# v_0_2.net
KiCad netlist of a schematic drawn in EAGLE
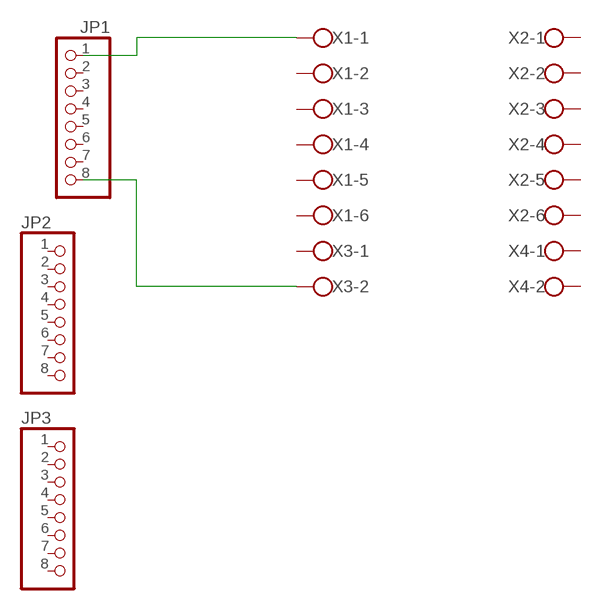
[diagram p0: schematic, sheet 1]

(export (version "E")
  (design (tool "Eeschema 10.0.6"))
  (components
    (comp (ref "JP1")
      (value "PINHD-1X8")
      (footprint "eagle-import:1X08")
      (libsource (lib "eagle-import") (part "PINHD-1X8"))
    )
    (comp (ref "JP2")
      (value "PINHD-1X8")
      (footprint "eagle-import:1X08")
      (libsource (lib "eagle-import") (part "PINHD-1X8"))
    )
    (comp (ref "JP3")
      (value "PINHD-1X8")
      (footprint "eagle-import:1X08")
      (libsource (lib "eagle-import") (part "PINHD-1X8"))
    )
    (comp (ref "X1")
      (value "W237-136")
      (footprint "eagle-import:W237-136")
      (fields (field (name "MPN") "237-136"))
      (libsource (lib "eagle-import") (part "W237-136"))
    )
    (comp (ref "X2")
      (value "W237-136")
      (footprint "eagle-import:W237-136")
      (fields (field (name "MPN") "237-136"))
      (libsource (lib "eagle-import") (part "W237-136"))
    )
    (comp (ref "X3")
      (value "W237-136")
      (footprint "eagle-import:W237-136")
      (fields (field (name "MPN") "237-136"))
      (libsource (lib "eagle-import") (part "W237-136"))
    )
    (comp (ref "X4")
      (value "W237-136")
      (footprint "eagle-import:W237-136")
      (fields (field (name "MPN") "237-136"))
      (libsource (lib "eagle-import") (part "W237-136"))
    )
  )
  (nets
    (net (code "1") (name "Net-(X1A-KL)") (class "Default")
      (node (ref "JP1") (pin "1") (pinfunction "1_1") (pintype "passive"))
      (node (ref "X1") (pin "1") (pinfunction "KL_1") (pintype "passive"))
    )
    (net (code "2") (name "Net-(X3B-KL)") (class "Default")
      (node (ref "JP1") (pin "8") (pinfunction "8_8") (pintype "passive"))
      (node (ref "X3") (pin "2") (pinfunction "KL_2") (pintype "passive"))
    )
    (net (code "3") (name "unconnected-(JP1-Pad2)") (class "Default")
      (node (ref "JP1") (pin "2") (pinfunction "2_2") (pintype "passive"))
    )
    (net (code "4") (name "unconnected-(JP1-Pad3)") (class "Default")
      (node (ref "JP1") (pin "3") (pinfunction "3_3") (pintype "passive"))
    )
    (net (code "5") (name "unconnected-(JP1-Pad4)") (class "Default")
      (node (ref "JP1") (pin "4") (pinfunction "4_4") (pintype "passive"))
    )
    (net (code "6") (name "unconnected-(JP1-Pad5)") (class "Default")
      (node (ref "JP1") (pin "5") (pinfunction "5_5") (pintype "passive"))
    )
    (net (code "7") (name "unconnected-(JP1-Pad6)") (class "Default")
      (node (ref "JP1") (pin "6") (pinfunction "6_6") (pintype "passive"))
    )
    (net (code "8") (name "unconnected-(JP1-Pad7)") (class "Default")
      (node (ref "JP1") (pin "7") (pinfunction "7_7") (pintype "passive"))
    )
    (net (code "9") (name "unconnected-(JP2-Pad1)") (class "Default")
      (node (ref "JP2") (pin "1") (pinfunction "1_1") (pintype "passive"))
    )
    (net (code "10") (name "unconnected-(JP2-Pad2)") (class "Default")
      (node (ref "JP2") (pin "2") (pinfunction "2_2") (pintype "passive"))
    )
    (net (code "11") (name "unconnected-(JP2-Pad3)") (class "Default")
      (node (ref "JP2") (pin "3") (pinfunction "3_3") (pintype "passive"))
    )
    (net (code "12") (name "unconnected-(JP2-Pad4)") (class "Default")
      (node (ref "JP2") (pin "4") (pinfunction "4_4") (pintype "passive"))
    )
    (net (code "13") (name "unconnected-(JP2-Pad5)") (class "Default")
      (node (ref "JP2") (pin "5") (pinfunction "5_5") (pintype "passive"))
    )
    (net (code "14") (name "unconnected-(JP2-Pad6)") (class "Default")
      (node (ref "JP2") (pin "6") (pinfunction "6_6") (pintype "passive"))
    )
    (net (code "15") (name "unconnected-(JP2-Pad7)") (class "Default")
      (node (ref "JP2") (pin "7") (pinfunction "7_7") (pintype "passive"))
    )
    (net (code "16") (name "unconnected-(JP2-Pad8)") (class "Default")
      (node (ref "JP2") (pin "8") (pinfunction "8_8") (pintype "passive"))
    )
    (net (code "17") (name "unconnected-(JP3-Pad1)") (class "Default")
      (node (ref "JP3") (pin "1") (pinfunction "1_1") (pintype "passive"))
    )
    (net (code "18") (name "unconnected-(JP3-Pad2)") (class "Default")
      (node (ref "JP3") (pin "2") (pinfunction "2_2") (pintype "passive"))
    )
    (net (code "19") (name "unconnected-(JP3-Pad3)") (class "Default")
      (node (ref "JP3") (pin "3") (pinfunction "3_3") (pintype "passive"))
    )
    (net (code "20") (name "unconnected-(JP3-Pad4)") (class "Default")
      (node (ref "JP3") (pin "4") (pinfunction "4_4") (pintype "passive"))
    )
    (net (code "21") (name "unconnected-(JP3-Pad5)") (class "Default")
      (node (ref "JP3") (pin "5") (pinfunction "5_5") (pintype "passive"))
    )
    (net (code "22") (name "unconnected-(JP3-Pad6)") (class "Default")
      (node (ref "JP3") (pin "6") (pinfunction "6_6") (pintype "passive"))
    )
    (net (code "23") (name "unconnected-(JP3-Pad7)") (class "Default")
      (node (ref "JP3") (pin "7") (pinfunction "7_7") (pintype "passive"))
    )
    (net (code "24") (name "unconnected-(JP3-Pad8)") (class "Default")
      (node (ref "JP3") (pin "8") (pinfunction "8_8") (pintype "passive"))
    )
    (net (code "25") (name "unconnected-(X1B-KL-Pad2)") (class "Default")
      (node (ref "X1") (pin "2") (pinfunction "KL_2") (pintype "passive"))
    )
    (net (code "26") (name "unconnected-(X1C-KL-Pad3)") (class "Default")
      (node (ref "X1") (pin "3") (pinfunction "KL_3") (pintype "passive"))
    )
    (net (code "27") (name "unconnected-(X1D-KL-Pad4)") (class "Default")
      (node (ref "X1") (pin "4") (pinfunction "KL_4") (pintype "passive"))
    )
    (net (code "28") (name "unconnected-(X1E-KL-Pad5)") (class "Default")
      (node (ref "X1") (pin "5") (pinfunction "KL_5") (pintype "passive"))
    )
    (net (code "29") (name "unconnected-(X1F-KL-Pad6)") (class "Default")
      (node (ref "X1") (pin "6") (pinfunction "KL_6") (pintype "passive"))
    )
    (net (code "30") (name "unconnected-(X2A-KL-Pad1)") (class "Default")
      (node (ref "X2") (pin "1") (pinfunction "KL_1") (pintype "passive"))
    )
    (net (code "31") (name "unconnected-(X2B-KL-Pad2)") (class "Default")
      (node (ref "X2") (pin "2") (pinfunction "KL_2") (pintype "passive"))
    )
    (net (code "32") (name "unconnected-(X2C-KL-Pad3)") (class "Default")
      (node (ref "X2") (pin "3") (pinfunction "KL_3") (pintype "passive"))
    )
    (net (code "33") (name "unconnected-(X2D-KL-Pad4)") (class "Default")
      (node (ref "X2") (pin "4") (pinfunction "KL_4") (pintype "passive"))
    )
    (net (code "34") (name "unconnected-(X2E-KL-Pad5)") (class "Default")
      (node (ref "X2") (pin "5") (pinfunction "KL_5") (pintype "passive"))
    )
    (net (code "35") (name "unconnected-(X2F-KL-Pad6)") (class "Default")
      (node (ref "X2") (pin "6") (pinfunction "KL_6") (pintype "passive"))
    )
    (net (code "36") (name "unconnected-(X3A-KL-Pad1)") (class "Default")
      (node (ref "X3") (pin "1") (pinfunction "KL_1") (pintype "passive"))
    )
    (net (code "37") (name "unconnected-(X4A-KL-Pad1)") (class "Default")
      (node (ref "X4") (pin "1") (pinfunction "KL_1") (pintype "passive"))
    )
    (net (code "38") (name "unconnected-(X4B-KL-Pad2)") (class "Default")
      (node (ref "X4") (pin "2") (pinfunction "KL_2") (pintype "passive"))
    )
  )
)
